# Ex_Build_System_Lights.net
KiCad netlist of a schematic drawn in EAGLE
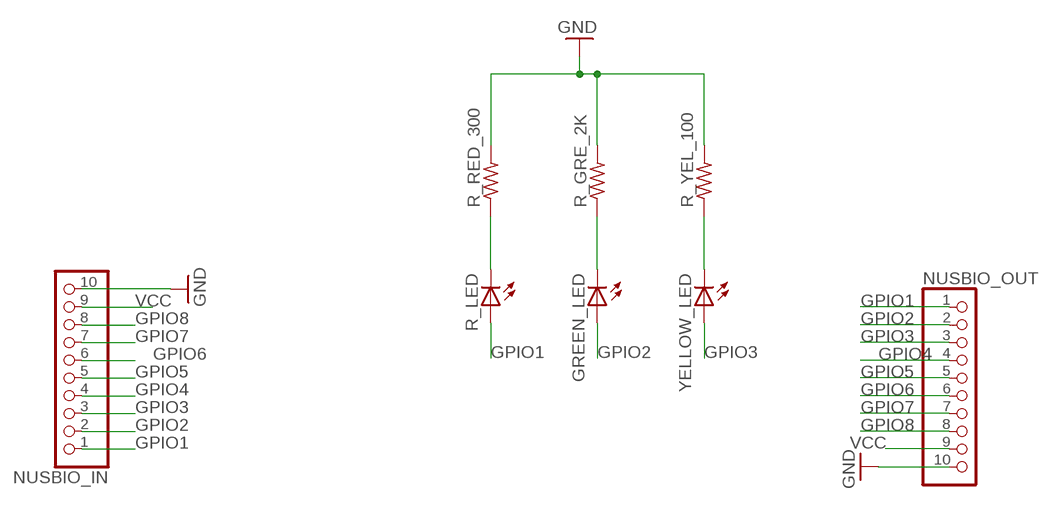
[diagram p0: schematic, sheet 1]

(export (version "E")
  (design (tool "Eeschema 10.0.6"))
  (components
    (comp (ref "GREEN_LED")
      (value "LED5MM")
      (footprint "eagle-import:LED5MM")
      (libsource (lib "eagle-import") (part "LED5MM"))
    )
    (comp (ref "NUSBIO_IN")
      (value "PINHD-1X10")
      (footprint "eagle-import:1X10-BIG")
      (libsource (lib "eagle-import") (part "PINHD-1X10"))
    )
    (comp (ref "NUSBIO_OUT")
      (value "PINHD-1X10")
      (footprint "eagle-import:1X10-BIG")
      (libsource (lib "eagle-import") (part "PINHD-1X10"))
    )
    (comp (ref "R_GRE_2K")
      (value "R-US_R1206")
      (footprint "eagle-import:R1206")
      (libsource (lib "eagle-import") (part "R-US_R1206"))
    )
    (comp (ref "R_LED")
      (value "LED5MM")
      (footprint "eagle-import:LED5MM")
      (libsource (lib "eagle-import") (part "LED5MM"))
    )
    (comp (ref "R_RED_300")
      (value "R-US_R1206")
      (footprint "eagle-import:R1206")
      (libsource (lib "eagle-import") (part "R-US_R1206"))
    )
    (comp (ref "R_YEL_100")
      (value "R-US_R1206")
      (footprint "eagle-import:R1206")
      (libsource (lib "eagle-import") (part "R-US_R1206"))
    )
    (comp (ref "YELLOW_LED")
      (value "LED5MM")
      (footprint "eagle-import:LED5MM")
      (libsource (lib "eagle-import") (part "LED5MM"))
    )
  )
  (nets
    (net (code "1") (name "/GPIO1") (class "Default")
      (node (ref "NUSBIO_IN") (pin "1") (pinfunction "1_1") (pintype "passive"))
      (node (ref "NUSBIO_OUT") (pin "1") (pinfunction "1_1") (pintype "passive"))
      (node (ref "R_LED") (pin "A") (pinfunction "A_A") (pintype "passive"))
    )
    (net (code "2") (name "/GPIO2") (class "Default")
      (node (ref "GREEN_LED") (pin "A") (pinfunction "A_A") (pintype "passive"))
      (node (ref "NUSBIO_IN") (pin "2") (pinfunction "2_2") (pintype "passive"))
      (node (ref "NUSBIO_OUT") (pin "2") (pinfunction "2_2") (pintype "passive"))
    )
    (net (code "3") (name "/GPIO3") (class "Default")
      (node (ref "NUSBIO_IN") (pin "3") (pinfunction "3_3") (pintype "passive"))
      (node (ref "NUSBIO_OUT") (pin "3") (pinfunction "3_3") (pintype "passive"))
      (node (ref "YELLOW_LED") (pin "A") (pinfunction "A_A") (pintype "passive"))
    )
    (net (code "4") (name "/GPIO4") (class "Default")
      (node (ref "NUSBIO_IN") (pin "4") (pinfunction "4_4") (pintype "passive"))
      (node (ref "NUSBIO_OUT") (pin "4") (pinfunction "4_4") (pintype "passive"))
    )
    (net (code "5") (name "/GPIO5") (class "Default")
      (node (ref "NUSBIO_IN") (pin "5") (pinfunction "5_5") (pintype "passive"))
      (node (ref "NUSBIO_OUT") (pin "5") (pinfunction "5_5") (pintype "passive"))
    )
    (net (code "6") (name "/GPIO6") (class "Default")
      (node (ref "NUSBIO_IN") (pin "6") (pinfunction "6_6") (pintype "passive"))
      (node (ref "NUSBIO_OUT") (pin "6") (pinfunction "6_6") (pintype "passive"))
    )
    (net (code "7") (name "/GPIO7") (class "Default")
      (node (ref "NUSBIO_IN") (pin "7") (pinfunction "7_7") (pintype "passive"))
      (node (ref "NUSBIO_OUT") (pin "7") (pinfunction "7_7") (pintype "passive"))
    )
    (net (code "8") (name "/GPIO8") (class "Default")
      (node (ref "NUSBIO_IN") (pin "8") (pinfunction "8_8") (pintype "passive"))
      (node (ref "NUSBIO_OUT") (pin "8") (pinfunction "8_8") (pintype "passive"))
    )
    (net (code "9") (name "/VCC") (class "Default")
      (node (ref "NUSBIO_IN") (pin "9") (pinfunction "9_9") (pintype "passive"))
      (node (ref "NUSBIO_OUT") (pin "9") (pinfunction "9_9") (pintype "passive"))
    )
    (net (code "10") (name "GND") (class "Default")
      (node (ref "NUSBIO_IN") (pin "10") (pinfunction "10_10") (pintype "passive"))
      (node (ref "NUSBIO_OUT") (pin "10") (pinfunction "10_10") (pintype "passive"))
      (node (ref "R_GRE_2K") (pin "2") (pinfunction "2_2") (pintype "passive"))
      (node (ref "R_RED_300") (pin "2") (pinfunction "2_2") (pintype "passive"))
      (node (ref "R_YEL_100") (pin "2") (pinfunction "2_2") (pintype "passive"))
    )
    (net (code "11") (name "Net-(GREEN_LED-C)") (class "Default")
      (node (ref "GREEN_LED") (pin "K") (pinfunction "C_K") (pintype "passive"))
      (node (ref "R_GRE_2K") (pin "1") (pinfunction "1_1") (pintype "passive"))
    )
    (net (code "12") (name "Net-(R_LED-C)") (class "Default")
      (node (ref "R_LED") (pin "K") (pinfunction "C_K") (pintype "passive"))
      (node (ref "R_RED_300") (pin "1") (pinfunction "1_1") (pintype "passive"))
    )
    (net (code "13") (name "Net-(YELLOW_LED-C)") (class "Default")
      (node (ref "R_YEL_100") (pin "1") (pinfunction "1_1") (pintype "passive"))
      (node (ref "YELLOW_LED") (pin "K") (pinfunction "C_K") (pintype "passive"))
    )
  )
)
